# schem1.net
KiCad netlist of a schematic drawn in EAGLE
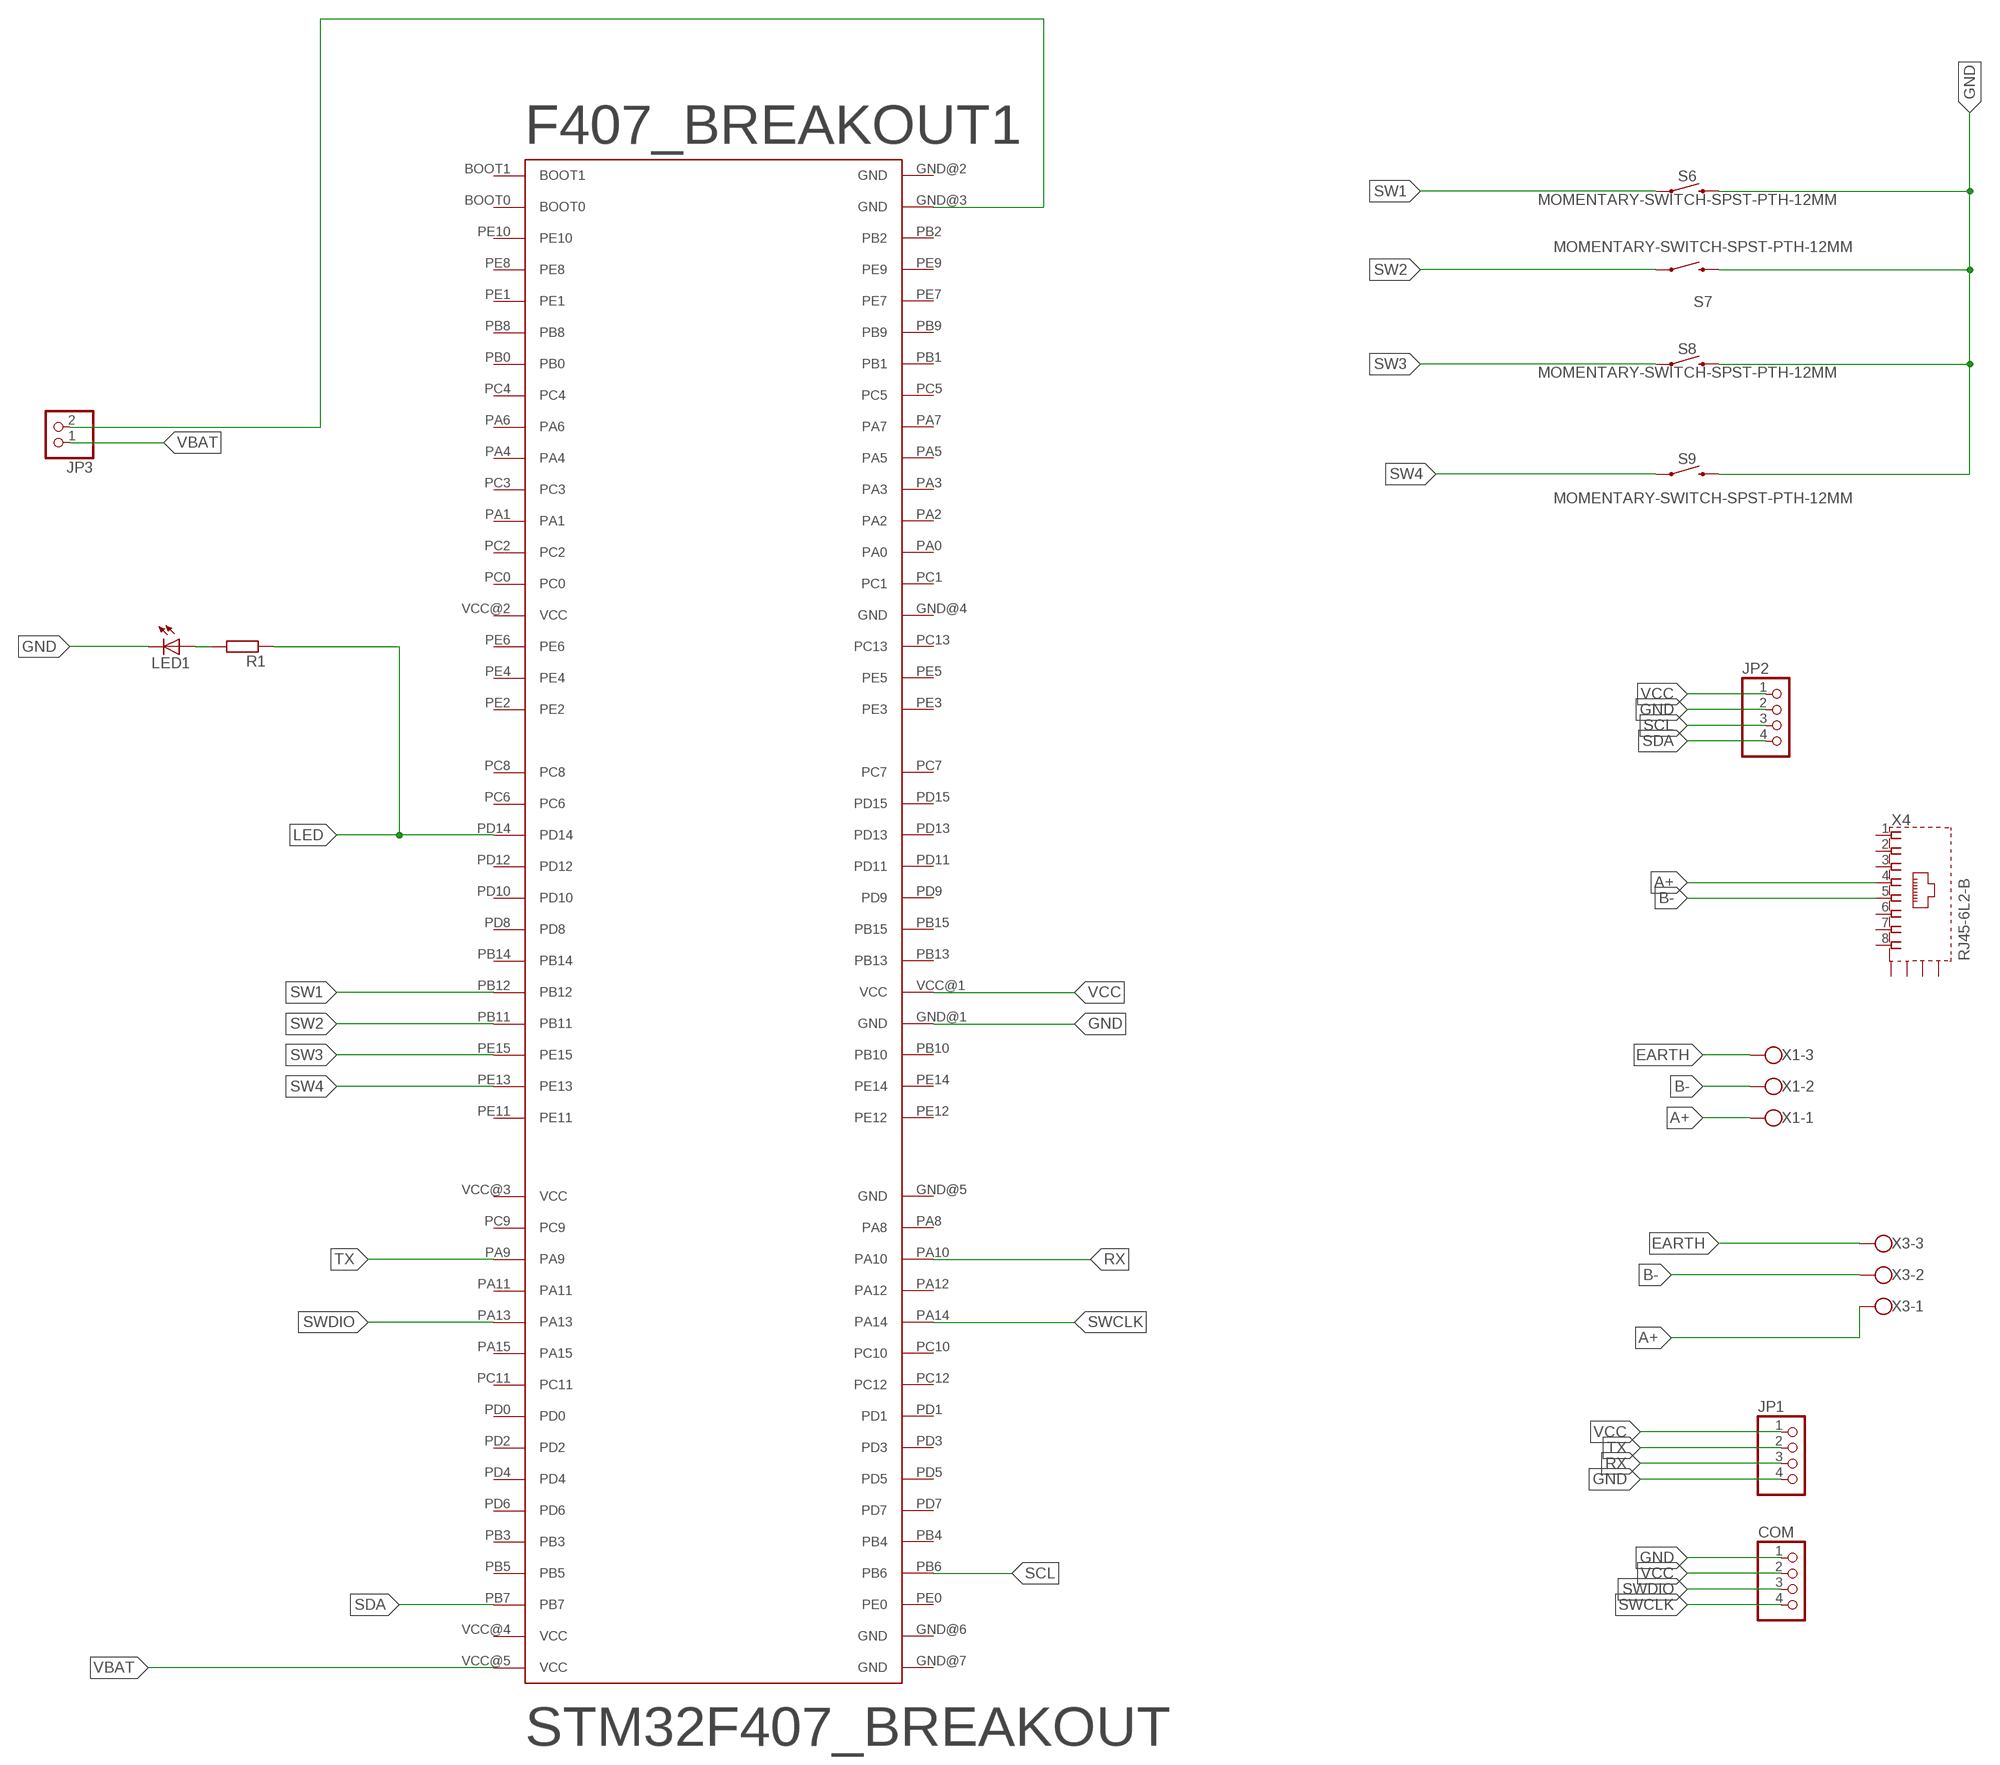
[diagram p0: schematic, sheet 1]

(export (version "E")
  (design (tool "Eeschema 10.0.6"))
  (components
    (comp (ref "COM")
      (value "PINHD-1X4")
      (footprint "eagle-import:1X04")
      (libsource (lib "eagle-import") (part "PINHD-1X4"))
    )
    (comp (ref "F407_BREAKOUT1")
      (value "STM32F407_BREAKOUT")
      (footprint "eagle-import:STM32F407_BREAKOUT")
      (libsource (lib "eagle-import") (part "STM32F407_BREAKOUT"))
    )
    (comp (ref "JP1")
      (value "PINHD-1X4")
      (footprint "eagle-import:1X04")
      (libsource (lib "eagle-import") (part "PINHD-1X4"))
    )
    (comp (ref "JP2")
      (value "PINHD-1X4")
      (footprint "eagle-import:1X04")
      (libsource (lib "eagle-import") (part "PINHD-1X4"))
    )
    (comp (ref "JP3")
      (value "PINHD-1X2")
      (footprint "eagle-import:1X02")
      (libsource (lib "eagle-import") (part "PINHD-1X2"))
    )
    (comp (ref "LED1")
      (value "LED3MM")
      (footprint "eagle-import:LED3MM")
      (libsource (lib "eagle-import") (part "LED3MM"))
    )
    (comp (ref "R1")
      (value "R-EU_0207/10")
      (footprint "eagle-import:0207_10")
      (libsource (lib "eagle-import") (part "R-EU_0207/10"))
    )
    (comp (ref "S6")
      (value "MOMENTARY-SWITCH-SPST-PTH-12MM")
      (footprint "eagle-import:TACTILE_SWITCH_PTH_12MM")
      (libsource (lib "eagle-import") (part "MOMENTARY-SWITCH-SPST-PTH-12MM"))
    )
    (comp (ref "S7")
      (value "MOMENTARY-SWITCH-SPST-PTH-12MM")
      (footprint "eagle-import:TACTILE_SWITCH_PTH_12MM")
      (libsource (lib "eagle-import") (part "MOMENTARY-SWITCH-SPST-PTH-12MM"))
    )
    (comp (ref "S8")
      (value "MOMENTARY-SWITCH-SPST-PTH-12MM")
      (footprint "eagle-import:TACTILE_SWITCH_PTH_12MM")
      (libsource (lib "eagle-import") (part "MOMENTARY-SWITCH-SPST-PTH-12MM"))
    )
    (comp (ref "S9")
      (value "MOMENTARY-SWITCH-SPST-PTH-12MM")
      (footprint "eagle-import:TACTILE_SWITCH_PTH_12MM")
      (libsource (lib "eagle-import") (part "MOMENTARY-SWITCH-SPST-PTH-12MM"))
    )
    (comp (ref "X1")
      (value "W237-103")
      (footprint "eagle-import:W237-103")
      (fields (field (name "MPN") "237-103"))
      (libsource (lib "eagle-import") (part "W237-103"))
    )
    (comp (ref "X3")
      (value "W237-103")
      (footprint "eagle-import:W237-103")
      (fields (field (name "MPN") "237-103"))
      (libsource (lib "eagle-import") (part "W237-103"))
    )
    (comp (ref "X4")
      (value "RJ45-6L2-B")
      (footprint "eagle-import:RJ45-SHIELD2")
      (libsource (lib "eagle-import") (part "RJ452-B-6L"))
    )
  )
  (nets
    (net (code "1") (name "A+") (class "Default")
      (node (ref "X1") (pin "1") (pinfunction "KL_1") (pintype "passive"))
      (node (ref "X3") (pin "1") (pinfunction "KL_1") (pintype "passive"))
      (node (ref "X4") (pin "4") (pinfunction "4_4") (pintype "passive"))
    )
    (net (code "2") (name "B-") (class "Default")
      (node (ref "X1") (pin "2") (pinfunction "KL_2") (pintype "passive"))
      (node (ref "X3") (pin "2") (pinfunction "KL_2") (pintype "passive"))
      (node (ref "X4") (pin "5") (pinfunction "5_5") (pintype "passive"))
    )
    (net (code "3") (name "EARTH") (class "Default")
      (node (ref "X1") (pin "3") (pinfunction "KL_3") (pintype "passive"))
      (node (ref "X3") (pin "3") (pinfunction "KL_3") (pintype "passive"))
    )
    (net (code "4") (name "GND") (class "Default")
      (node (ref "COM") (pin "1") (pinfunction "1_1") (pintype "passive"))
      (node (ref "F407_BREAKOUT1") (pin "GND@1") (pinfunction "GND_GND@1") (pintype "bidirectional"))
      (node (ref "JP1") (pin "4") (pinfunction "4_4") (pintype "passive"))
      (node (ref "JP2") (pin "2") (pinfunction "2_2") (pintype "passive"))
      (node (ref "LED1") (pin "K") (pinfunction "C_K") (pintype "passive"))
      (node (ref "S6") (pin "3") (pinfunction "2_3") (pintype "passive"))
      (node (ref "S7") (pin "3") (pinfunction "2_3") (pintype "passive"))
      (node (ref "S8") (pin "3") (pinfunction "2_3") (pintype "passive"))
      (node (ref "S9") (pin "3") (pinfunction "2_3") (pintype "passive"))
    )
    (net (code "5") (name "LED") (class "Default")
      (node (ref "F407_BREAKOUT1") (pin "PD14") (pinfunction "PD14_PD14") (pintype "bidirectional"))
      (node (ref "R1") (pin "1") (pinfunction "1_1") (pintype "passive"))
    )
    (net (code "6") (name "Net-(F407_BREAKOUT1-GND-PadGND@3)") (class "Default")
      (node (ref "F407_BREAKOUT1") (pin "GND@3") (pinfunction "GND_GND@3") (pintype "bidirectional"))
      (node (ref "JP3") (pin "2") (pinfunction "2_2") (pintype "passive"))
    )
    (net (code "7") (name "Net-(LED1-PadA)") (class "Default")
      (node (ref "LED1") (pin "A") (pinfunction "A_A") (pintype "passive"))
      (node (ref "R1") (pin "2") (pinfunction "2_2") (pintype "passive"))
    )
    (net (code "8") (name "RX") (class "Default")
      (node (ref "F407_BREAKOUT1") (pin "PA10") (pinfunction "PA10_PA10") (pintype "bidirectional"))
      (node (ref "JP1") (pin "3") (pinfunction "3_3") (pintype "passive"))
    )
    (net (code "9") (name "SCL") (class "Default")
      (node (ref "F407_BREAKOUT1") (pin "PB6") (pinfunction "PB6_PB6") (pintype "bidirectional"))
      (node (ref "JP2") (pin "3") (pinfunction "3_3") (pintype "passive"))
    )
    (net (code "10") (name "SDA") (class "Default")
      (node (ref "F407_BREAKOUT1") (pin "PB7") (pinfunction "PB7_PB7") (pintype "bidirectional"))
      (node (ref "JP2") (pin "4") (pinfunction "4_4") (pintype "passive"))
    )
    (net (code "11") (name "SW1") (class "Default")
      (node (ref "F407_BREAKOUT1") (pin "PB12") (pinfunction "PB12_PB12") (pintype "bidirectional"))
      (node (ref "S6") (pin "1") (pinfunction "1_1") (pintype "passive"))
    )
    (net (code "12") (name "SW2") (class "Default")
      (node (ref "F407_BREAKOUT1") (pin "PB11") (pinfunction "PB11_PB11") (pintype "bidirectional"))
      (node (ref "S7") (pin "1") (pinfunction "1_1") (pintype "passive"))
    )
    (net (code "13") (name "SW3") (class "Default")
      (node (ref "F407_BREAKOUT1") (pin "PE15") (pinfunction "PE15_PE15") (pintype "bidirectional"))
      (node (ref "S8") (pin "1") (pinfunction "1_1") (pintype "passive"))
    )
    (net (code "14") (name "SW4") (class "Default")
      (node (ref "F407_BREAKOUT1") (pin "PE13") (pinfunction "PE13_PE13") (pintype "bidirectional"))
      (node (ref "S9") (pin "1") (pinfunction "1_1") (pintype "passive"))
    )
    (net (code "15") (name "SWCLK") (class "Default")
      (node (ref "COM") (pin "4") (pinfunction "4_4") (pintype "passive"))
      (node (ref "F407_BREAKOUT1") (pin "PA14") (pinfunction "PA14_PA14") (pintype "bidirectional"))
    )
    (net (code "16") (name "SWDIO") (class "Default")
      (node (ref "COM") (pin "3") (pinfunction "3_3") (pintype "passive"))
      (node (ref "F407_BREAKOUT1") (pin "PA13") (pinfunction "PA13_PA13") (pintype "bidirectional"))
    )
    (net (code "17") (name "TX") (class "Default")
      (node (ref "F407_BREAKOUT1") (pin "PA9") (pinfunction "PA9_PA9") (pintype "bidirectional"))
      (node (ref "JP1") (pin "2") (pinfunction "2_2") (pintype "passive"))
    )
    (net (code "18") (name "VBAT") (class "Default")
      (node (ref "F407_BREAKOUT1") (pin "VCC@5") (pinfunction "VCC_VCC@5") (pintype "bidirectional"))
      (node (ref "JP3") (pin "1") (pinfunction "1_1") (pintype "passive"))
    )
    (net (code "19") (name "VCC") (class "Default")
      (node (ref "COM") (pin "2") (pinfunction "2_2") (pintype "passive"))
      (node (ref "F407_BREAKOUT1") (pin "VCC@1") (pinfunction "VCC_VCC@1") (pintype "bidirectional"))
      (node (ref "JP1") (pin "1") (pinfunction "1_1") (pintype "passive"))
      (node (ref "JP2") (pin "1") (pinfunction "1_1") (pintype "passive"))
    )
    (net (code "20") (name "unconnected-(F407_BREAKOUT1-GND-PadGND@2)") (class "Default")
      (node (ref "F407_BREAKOUT1") (pin "GND@2") (pinfunction "GND_GND@2") (pintype "bidirectional"))
    )
    (net (code "21") (name "unconnected-(F407_BREAKOUT1-GND-PadGND@4)") (class "Default")
      (node (ref "F407_BREAKOUT1") (pin "GND@4") (pinfunction "GND_GND@4") (pintype "bidirectional"))
    )
    (net (code "22") (name "unconnected-(F407_BREAKOUT1-GND-PadGND@5)") (class "Default")
      (node (ref "F407_BREAKOUT1") (pin "GND@5") (pinfunction "GND_GND@5") (pintype "bidirectional"))
    )
    (net (code "23") (name "unconnected-(F407_BREAKOUT1-GND-PadGND@6)") (class "Default")
      (node (ref "F407_BREAKOUT1") (pin "GND@6") (pinfunction "GND_GND@6") (pintype "bidirectional"))
    )
    (net (code "24") (name "unconnected-(F407_BREAKOUT1-GND-PadGND@7)") (class "Default")
      (node (ref "F407_BREAKOUT1") (pin "GND@7") (pinfunction "GND_GND@7") (pintype "bidirectional"))
    )
    (net (code "25") (name "unconnected-(F407_BREAKOUT1-PadBOOT0)") (class "Default")
      (node (ref "F407_BREAKOUT1") (pin "BOOT0") (pinfunction "BOOT0_BOOT0") (pintype "bidirectional"))
    )
    (net (code "26") (name "unconnected-(F407_BREAKOUT1-PadBOOT1)") (class "Default")
      (node (ref "F407_BREAKOUT1") (pin "BOOT1") (pinfunction "BOOT1_BOOT1") (pintype "bidirectional"))
    )
    (net (code "27") (name "unconnected-(F407_BREAKOUT1-PadPA0)") (class "Default")
      (node (ref "F407_BREAKOUT1") (pin "PA0") (pinfunction "PA0_PA0") (pintype "bidirectional"))
    )
    (net (code "28") (name "unconnected-(F407_BREAKOUT1-PadPA1)") (class "Default")
      (node (ref "F407_BREAKOUT1") (pin "PA1") (pinfunction "PA1_PA1") (pintype "bidirectional"))
    )
    (net (code "29") (name "unconnected-(F407_BREAKOUT1-PadPA2)") (class "Default")
      (node (ref "F407_BREAKOUT1") (pin "PA2") (pinfunction "PA2_PA2") (pintype "bidirectional"))
    )
    (net (code "30") (name "unconnected-(F407_BREAKOUT1-PadPA3)") (class "Default")
      (node (ref "F407_BREAKOUT1") (pin "PA3") (pinfunction "PA3_PA3") (pintype "bidirectional"))
    )
    (net (code "31") (name "unconnected-(F407_BREAKOUT1-PadPA4)") (class "Default")
      (node (ref "F407_BREAKOUT1") (pin "PA4") (pinfunction "PA4_PA4") (pintype "bidirectional"))
    )
    (net (code "32") (name "unconnected-(F407_BREAKOUT1-PadPA5)") (class "Default")
      (node (ref "F407_BREAKOUT1") (pin "PA5") (pinfunction "PA5_PA5") (pintype "bidirectional"))
    )
    (net (code "33") (name "unconnected-(F407_BREAKOUT1-PadPA6)") (class "Default")
      (node (ref "F407_BREAKOUT1") (pin "PA6") (pinfunction "PA6_PA6") (pintype "bidirectional"))
    )
    (net (code "34") (name "unconnected-(F407_BREAKOUT1-PadPA7)") (class "Default")
      (node (ref "F407_BREAKOUT1") (pin "PA7") (pinfunction "PA7_PA7") (pintype "bidirectional"))
    )
    (net (code "35") (name "unconnected-(F407_BREAKOUT1-PadPA8)") (class "Default")
      (node (ref "F407_BREAKOUT1") (pin "PA8") (pinfunction "PA8_PA8") (pintype "bidirectional"))
    )
    (net (code "36") (name "unconnected-(F407_BREAKOUT1-PadPA11)") (class "Default")
      (node (ref "F407_BREAKOUT1") (pin "PA11") (pinfunction "PA11_PA11") (pintype "bidirectional"))
    )
    (net (code "37") (name "unconnected-(F407_BREAKOUT1-PadPA12)") (class "Default")
      (node (ref "F407_BREAKOUT1") (pin "PA12") (pinfunction "PA12_PA12") (pintype "bidirectional"))
    )
    (net (code "38") (name "unconnected-(F407_BREAKOUT1-PadPA15)") (class "Default")
      (node (ref "F407_BREAKOUT1") (pin "PA15") (pinfunction "PA15_PA15") (pintype "bidirectional"))
    )
    (net (code "39") (name "unconnected-(F407_BREAKOUT1-PadPB0)") (class "Default")
      (node (ref "F407_BREAKOUT1") (pin "PB0") (pinfunction "PB0_PB0") (pintype "bidirectional"))
    )
    (net (code "40") (name "unconnected-(F407_BREAKOUT1-PadPB1)") (class "Default")
      (node (ref "F407_BREAKOUT1") (pin "PB1") (pinfunction "PB1_PB1") (pintype "bidirectional"))
    )
    (net (code "41") (name "unconnected-(F407_BREAKOUT1-PadPB2)") (class "Default")
      (node (ref "F407_BREAKOUT1") (pin "PB2") (pinfunction "PB2_PB2") (pintype "bidirectional"))
    )
    (net (code "42") (name "unconnected-(F407_BREAKOUT1-PadPB3)") (class "Default")
      (node (ref "F407_BREAKOUT1") (pin "PB3") (pinfunction "PB3_PB3") (pintype "bidirectional"))
    )
    (net (code "43") (name "unconnected-(F407_BREAKOUT1-PadPB4)") (class "Default")
      (node (ref "F407_BREAKOUT1") (pin "PB4") (pinfunction "PB4_PB4") (pintype "bidirectional"))
    )
    (net (code "44") (name "unconnected-(F407_BREAKOUT1-PadPB5)") (class "Default")
      (node (ref "F407_BREAKOUT1") (pin "PB5") (pinfunction "PB5_PB5") (pintype "bidirectional"))
    )
    (net (code "45") (name "unconnected-(F407_BREAKOUT1-PadPB8)") (class "Default")
      (node (ref "F407_BREAKOUT1") (pin "PB8") (pinfunction "PB8_PB8") (pintype "bidirectional"))
    )
    (net (code "46") (name "unconnected-(F407_BREAKOUT1-PadPB9)") (class "Default")
      (node (ref "F407_BREAKOUT1") (pin "PB9") (pinfunction "PB9_PB9") (pintype "bidirectional"))
    )
    (net (code "47") (name "unconnected-(F407_BREAKOUT1-PadPB10)") (class "Default")
      (node (ref "F407_BREAKOUT1") (pin "PB10") (pinfunction "PB10_PB10") (pintype "bidirectional"))
    )
    (net (code "48") (name "unconnected-(F407_BREAKOUT1-PadPB13)") (class "Default")
      (node (ref "F407_BREAKOUT1") (pin "PB13") (pinfunction "PB13_PB13") (pintype "bidirectional"))
    )
    (net (code "49") (name "unconnected-(F407_BREAKOUT1-PadPB14)") (class "Default")
      (node (ref "F407_BREAKOUT1") (pin "PB14") (pinfunction "PB14_PB14") (pintype "bidirectional"))
    )
    (net (code "50") (name "unconnected-(F407_BREAKOUT1-PadPB15)") (class "Default")
      (node (ref "F407_BREAKOUT1") (pin "PB15") (pinfunction "PB15_PB15") (pintype "bidirectional"))
    )
    (net (code "51") (name "unconnected-(F407_BREAKOUT1-PadPC0)") (class "Default")
      (node (ref "F407_BREAKOUT1") (pin "PC0") (pinfunction "PC0_PC0") (pintype "bidirectional"))
    )
    (net (code "52") (name "unconnected-(F407_BREAKOUT1-PadPC1)") (class "Default")
      (node (ref "F407_BREAKOUT1") (pin "PC1") (pinfunction "PC1_PC1") (pintype "bidirectional"))
    )
    (net (code "53") (name "unconnected-(F407_BREAKOUT1-PadPC2)") (class "Default")
      (node (ref "F407_BREAKOUT1") (pin "PC2") (pinfunction "PC2_PC2") (pintype "bidirectional"))
    )
    (net (code "54") (name "unconnected-(F407_BREAKOUT1-PadPC3)") (class "Default")
      (node (ref "F407_BREAKOUT1") (pin "PC3") (pinfunction "PC3_PC3") (pintype "bidirectional"))
    )
    (net (code "55") (name "unconnected-(F407_BREAKOUT1-PadPC4)") (class "Default")
      (node (ref "F407_BREAKOUT1") (pin "PC4") (pinfunction "PC4_PC4") (pintype "bidirectional"))
    )
    (net (code "56") (name "unconnected-(F407_BREAKOUT1-PadPC5)") (class "Default")
      (node (ref "F407_BREAKOUT1") (pin "PC5") (pinfunction "PC5_PC5") (pintype "bidirectional"))
    )
    (net (code "57") (name "unconnected-(F407_BREAKOUT1-PadPC6)") (class "Default")
      (node (ref "F407_BREAKOUT1") (pin "PC6") (pinfunction "PC6_PC6") (pintype "bidirectional"))
    )
    (net (code "58") (name "unconnected-(F407_BREAKOUT1-PadPC7)") (class "Default")
      (node (ref "F407_BREAKOUT1") (pin "PC7") (pinfunction "PC7_PC7") (pintype "bidirectional"))
    )
    (net (code "59") (name "unconnected-(F407_BREAKOUT1-PadPC8)") (class "Default")
      (node (ref "F407_BREAKOUT1") (pin "PC8") (pinfunction "PC8_PC8") (pintype "bidirectional"))
    )
    (net (code "60") (name "unconnected-(F407_BREAKOUT1-PadPC9)") (class "Default")
      (node (ref "F407_BREAKOUT1") (pin "PC9") (pinfunction "PC9_PC9") (pintype "bidirectional"))
    )
    (net (code "61") (name "unconnected-(F407_BREAKOUT1-PadPC10)") (class "Default")
      (node (ref "F407_BREAKOUT1") (pin "PC10") (pinfunction "PC10_PC10") (pintype "bidirectional"))
    )
    (net (code "62") (name "unconnected-(F407_BREAKOUT1-PadPC11)") (class "Default")
      (node (ref "F407_BREAKOUT1") (pin "PC11") (pinfunction "PC11_PC11") (pintype "bidirectional"))
    )
    (net (code "63") (name "unconnected-(F407_BREAKOUT1-PadPC12)") (class "Default")
      (node (ref "F407_BREAKOUT1") (pin "PC12") (pinfunction "PC12_PC12") (pintype "bidirectional"))
    )
    (net (code "64") (name "unconnected-(F407_BREAKOUT1-PadPC13)") (class "Default")
      (node (ref "F407_BREAKOUT1") (pin "PC13") (pinfunction "PC13_PC13") (pintype "bidirectional"))
    )
    (net (code "65") (name "unconnected-(F407_BREAKOUT1-PadPD0)") (class "Default")
      (node (ref "F407_BREAKOUT1") (pin "PD0") (pinfunction "PD0_PD0") (pintype "bidirectional"))
    )
    (net (code "66") (name "unconnected-(F407_BREAKOUT1-PadPD1)") (class "Default")
      (node (ref "F407_BREAKOUT1") (pin "PD1") (pinfunction "PD1_PD1") (pintype "bidirectional"))
    )
    (net (code "67") (name "unconnected-(F407_BREAKOUT1-PadPD2)") (class "Default")
      (node (ref "F407_BREAKOUT1") (pin "PD2") (pinfunction "PD2_PD2") (pintype "bidirectional"))
    )
    (net (code "68") (name "unconnected-(F407_BREAKOUT1-PadPD3)") (class "Default")
      (node (ref "F407_BREAKOUT1") (pin "PD3") (pinfunction "PD3_PD3") (pintype "bidirectional"))
    )
    (net (code "69") (name "unconnected-(F407_BREAKOUT1-PadPD4)") (class "Default")
      (node (ref "F407_BREAKOUT1") (pin "PD4") (pinfunction "PD4_PD4") (pintype "bidirectional"))
    )
    (net (code "70") (name "unconnected-(F407_BREAKOUT1-PadPD5)") (class "Default")
      (node (ref "F407_BREAKOUT1") (pin "PD5") (pinfunction "PD5_PD5") (pintype "bidirectional"))
    )
    (net (code "71") (name "unconnected-(F407_BREAKOUT1-PadPD6)") (class "Default")
      (node (ref "F407_BREAKOUT1") (pin "PD6") (pinfunction "PD6_PD6") (pintype "bidirectional"))
    )
    (net (code "72") (name "unconnected-(F407_BREAKOUT1-PadPD7)") (class "Default")
      (node (ref "F407_BREAKOUT1") (pin "PD7") (pinfunction "PD7_PD7") (pintype "bidirectional"))
    )
    (net (code "73") (name "unconnected-(F407_BREAKOUT1-PadPD8)") (class "Default")
      (node (ref "F407_BREAKOUT1") (pin "PD8") (pinfunction "PD8_PD8") (pintype "bidirectional"))
    )
    (net (code "74") (name "unconnected-(F407_BREAKOUT1-PadPD9)") (class "Default")
      (node (ref "F407_BREAKOUT1") (pin "PD9") (pinfunction "PD9_PD9") (pintype "bidirectional"))
    )
    (net (code "75") (name "unconnected-(F407_BREAKOUT1-PadPD10)") (class "Default")
      (node (ref "F407_BREAKOUT1") (pin "PD10") (pinfunction "PD10_PD10") (pintype "bidirectional"))
    )
    (net (code "76") (name "unconnected-(F407_BREAKOUT1-PadPD11)") (class "Default")
      (node (ref "F407_BREAKOUT1") (pin "PD11") (pinfunction "PD11_PD11") (pintype "bidirectional"))
    )
    (net (code "77") (name "unconnected-(F407_BREAKOUT1-PadPD12)") (class "Default")
      (node (ref "F407_BREAKOUT1") (pin "PD12") (pinfunction "PD12_PD12") (pintype "bidirectional"))
    )
    (net (code "78") (name "unconnected-(F407_BREAKOUT1-PadPD13)") (class "Default")
      (node (ref "F407_BREAKOUT1") (pin "PD13") (pinfunction "PD13_PD13") (pintype "bidirectional"))
    )
    (net (code "79") (name "unconnected-(F407_BREAKOUT1-PadPD15)") (class "Default")
      (node (ref "F407_BREAKOUT1") (pin "PD15") (pinfunction "PD15_PD15") (pintype "bidirectional"))
    )
    (net (code "80") (name "unconnected-(F407_BREAKOUT1-PadPE0)") (class "Default")
      (node (ref "F407_BREAKOUT1") (pin "PE0") (pinfunction "PE0_PE0") (pintype "bidirectional"))
    )
    (net (code "81") (name "unconnected-(F407_BREAKOUT1-PadPE1)") (class "Default")
      (node (ref "F407_BREAKOUT1") (pin "PE1") (pinfunction "PE1_PE1") (pintype "bidirectional"))
    )
    (net (code "82") (name "unconnected-(F407_BREAKOUT1-PadPE2)") (class "Default")
      (node (ref "F407_BREAKOUT1") (pin "PE2") (pinfunction "PE2_PE2") (pintype "bidirectional"))
    )
    (net (code "83") (name "unconnected-(F407_BREAKOUT1-PadPE3)") (class "Default")
      (node (ref "F407_BREAKOUT1") (pin "PE3") (pinfunction "PE3_PE3") (pintype "bidirectional"))
    )
    (net (code "84") (name "unconnected-(F407_BREAKOUT1-PadPE4)") (class "Default")
      (node (ref "F407_BREAKOUT1") (pin "PE4") (pinfunction "PE4_PE4") (pintype "bidirectional"))
    )
    (net (code "85") (name "unconnected-(F407_BREAKOUT1-PadPE5)") (class "Default")
      (node (ref "F407_BREAKOUT1") (pin "PE5") (pinfunction "PE5_PE5") (pintype "bidirectional"))
    )
    (net (code "86") (name "unconnected-(F407_BREAKOUT1-PadPE6)") (class "Default")
      (node (ref "F407_BREAKOUT1") (pin "PE6") (pinfunction "PE6_PE6") (pintype "bidirectional"))
    )
    (net (code "87") (name "unconnected-(F407_BREAKOUT1-PadPE7)") (class "Default")
      (node (ref "F407_BREAKOUT1") (pin "PE7") (pinfunction "PE7_PE7") (pintype "bidirectional"))
    )
    (net (code "88") (name "unconnected-(F407_BREAKOUT1-PadPE8)") (class "Default")
      (node (ref "F407_BREAKOUT1") (pin "PE8") (pinfunction "PE8_PE8") (pintype "bidirectional"))
    )
    (net (code "89") (name "unconnected-(F407_BREAKOUT1-PadPE9)") (class "Default")
      (node (ref "F407_BREAKOUT1") (pin "PE9") (pinfunction "PE9_PE9") (pintype "bidirectional"))
    )
    (net (code "90") (name "unconnected-(F407_BREAKOUT1-PadPE10)") (class "Default")
      (node (ref "F407_BREAKOUT1") (pin "PE10") (pinfunction "PE10_PE10") (pintype "bidirectional"))
    )
    (net (code "91") (name "unconnected-(F407_BREAKOUT1-PadPE11)") (class "Default")
      (node (ref "F407_BREAKOUT1") (pin "PE11") (pinfunction "PE11_PE11") (pintype "bidirectional"))
    )
    (net (code "92") (name "unconnected-(F407_BREAKOUT1-PadPE12)") (class "Default")
      (node (ref "F407_BREAKOUT1") (pin "PE12") (pinfunction "PE12_PE12") (pintype "bidirectional"))
    )
    (net (code "93") (name "unconnected-(F407_BREAKOUT1-PadPE14)") (class "Default")
      (node (ref "F407_BREAKOUT1") (pin "PE14") (pinfunction "PE14_PE14") (pintype "bidirectional"))
    )
    (net (code "94") (name "unconnected-(F407_BREAKOUT1-VCC-PadVCC@2)") (class "Default")
      (node (ref "F407_BREAKOUT1") (pin "VCC@2") (pinfunction "VCC_VCC@2") (pintype "bidirectional"))
    )
    (net (code "95") (name "unconnected-(F407_BREAKOUT1-VCC-PadVCC@3)") (class "Default")
      (node (ref "F407_BREAKOUT1") (pin "VCC@3") (pinfunction "VCC_VCC@3") (pintype "bidirectional"))
    )
    (net (code "96") (name "unconnected-(F407_BREAKOUT1-VCC-PadVCC@4)") (class "Default")
      (node (ref "F407_BREAKOUT1") (pin "VCC@4") (pinfunction "VCC_VCC@4") (pintype "bidirectional"))
    )
    (net (code "97") (name "unconnected-(X4-Pad1)") (class "Default")
      (node (ref "X4") (pin "1") (pinfunction "1_1") (pintype "passive"))
    )
    (net (code "98") (name "unconnected-(X4-Pad2)") (class "Default")
      (node (ref "X4") (pin "2") (pinfunction "2_2") (pintype "passive"))
    )
    (net (code "99") (name "unconnected-(X4-Pad3)") (class "Default")
      (node (ref "X4") (pin "3") (pinfunction "3_3") (pintype "passive"))
    )
    (net (code "100") (name "unconnected-(X4-Pad6)") (class "Default")
      (node (ref "X4") (pin "6") (pinfunction "6_6") (pintype "passive"))
    )
    (net (code "101") (name "unconnected-(X4-Pad7)") (class "Default")
      (node (ref "X4") (pin "7") (pinfunction "7_7") (pintype "passive"))
    )
    (net (code "102") (name "unconnected-(X4-Pad8)") (class "Default")
      (node (ref "X4") (pin "8") (pinfunction "8_8") (pintype "passive"))
    )
    (net (code "103") (name "unconnected-(X4-S-PadS1)") (class "Default")
      (node (ref "X4") (pin "S1") (pinfunction "S_S1") (pintype "passive"))
    )
    (net (code "104") (name "unconnected-(X4-S-PadS2)") (class "Default")
      (node (ref "X4") (pin "S2") (pinfunction "S_S2") (pintype "passive"))
    )
    (net (code "105") (name "unconnected-(X4-S-PadS3)") (class "Default")
      (node (ref "X4") (pin "S3") (pinfunction "S_S3") (pintype "passive"))
    )
    (net (code "106") (name "unconnected-(X4-S-PadS4)") (class "Default")
      (node (ref "X4") (pin "S4") (pinfunction "S_S4") (pintype "passive"))
    )
  )
)
